# Ethernet.net
KiCad netlist of a schematic drawn in Altium Designer
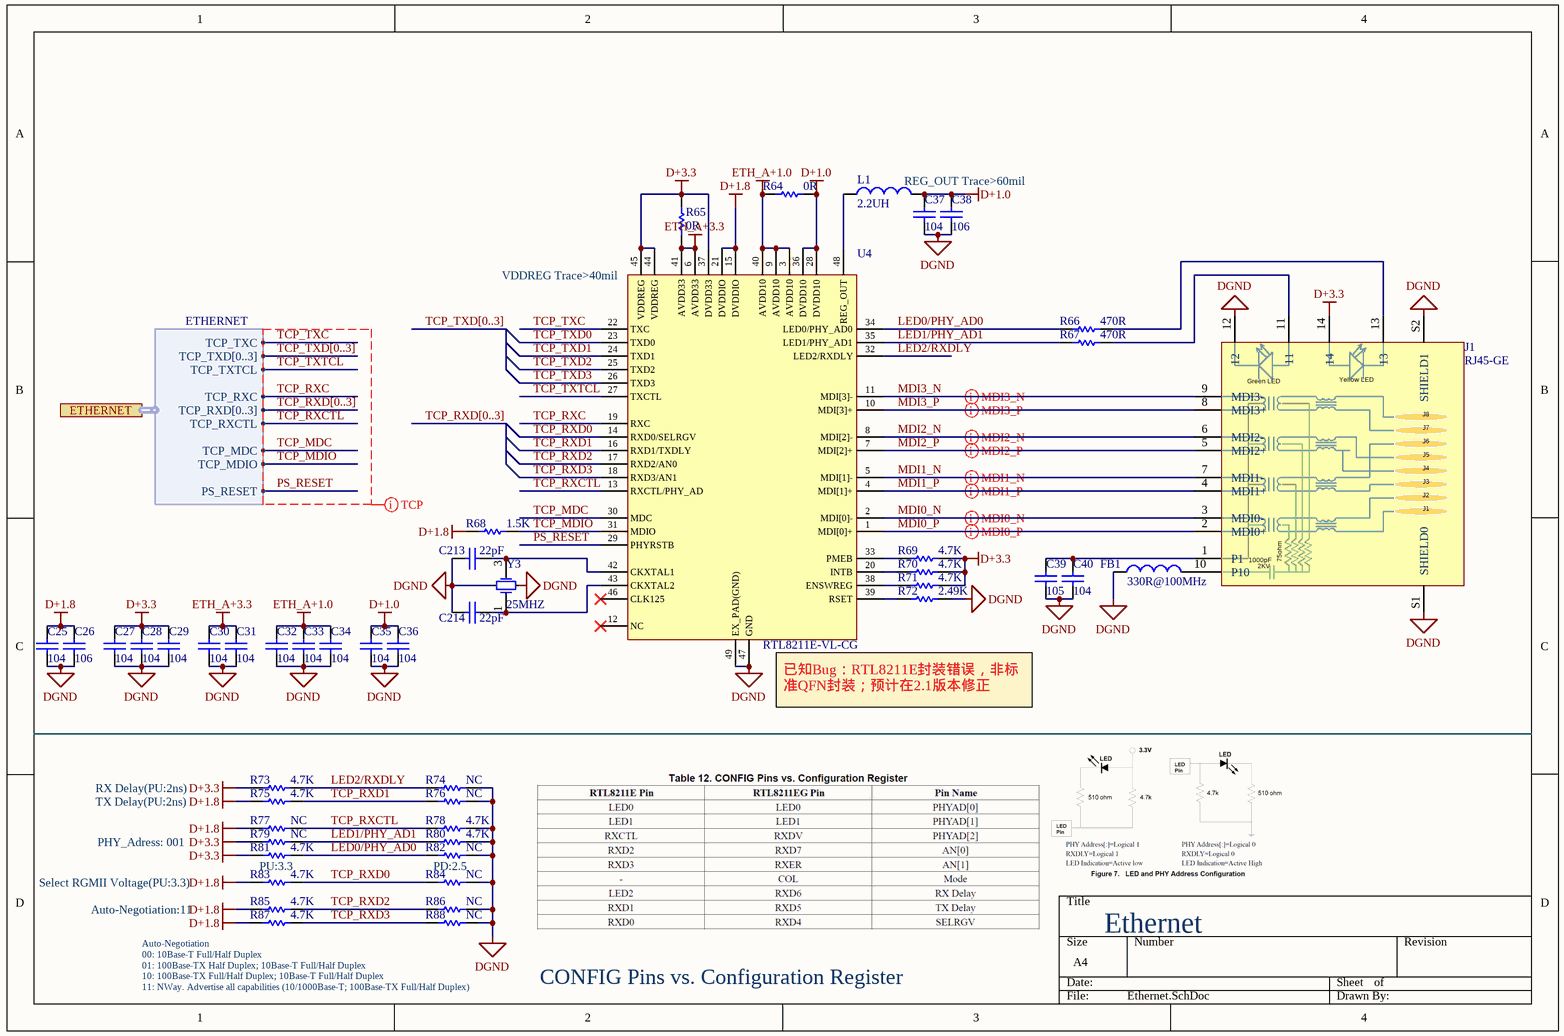
[diagram p0: Ethernet.SchDoc]

(export (version "E")
  (design (tool "Eeschema 10.0.6"))
  (components
    (comp (ref "C25")
      (value "104")
      (footprint "C 0402_LL")
      (description "Capacitor")
      (fields (field (name "PUBLISHER") "Altium Limited"))
      (libsource (lib "Miscellaneous Devices") (part "Cap"))
    )
    (comp (ref "C26")
      (value "106")
      (footprint "C 0603_L")
      (description "Capacitor")
      (fields (field (name "PUBLISHER") "Altium Limited"))
      (libsource (lib "Miscellaneous Devices") (part "Cap"))
    )
    (comp (ref "C27")
      (value "104")
      (footprint "C 0402_LL")
      (description "Capacitor")
      (fields (field (name "PUBLISHER") "Altium Limited"))
      (libsource (lib "Miscellaneous Devices") (part "Cap"))
    )
    (comp (ref "C28")
      (value "104")
      (footprint "C 0402_LL")
      (description "Capacitor")
      (fields (field (name "PUBLISHER") "Altium Limited"))
      (libsource (lib "Miscellaneous Devices") (part "Cap"))
    )
    (comp (ref "C29")
      (value "104")
      (footprint "C 0402_LL")
      (description "Capacitor")
      (fields (field (name "PUBLISHER") "Altium Limited"))
      (libsource (lib "Miscellaneous Devices") (part "Cap"))
    )
    (comp (ref "C30")
      (value "104")
      (footprint "C 0402_LL")
      (description "Capacitor")
      (fields (field (name "PUBLISHER") "Altium Limited"))
      (libsource (lib "Miscellaneous Devices") (part "Cap"))
    )
    (comp (ref "C31")
      (value "104")
      (footprint "C 0402_LL")
      (description "Capacitor")
      (fields (field (name "PUBLISHER") "Altium Limited"))
      (libsource (lib "Miscellaneous Devices") (part "Cap"))
    )
    (comp (ref "C32")
      (value "104")
      (footprint "C 0402_LL")
      (description "Capacitor")
      (fields (field (name "PUBLISHER") "Altium Limited"))
      (libsource (lib "Miscellaneous Devices") (part "Cap"))
    )
    (comp (ref "C33")
      (value "104")
      (footprint "C 0402_LL")
      (description "Capacitor")
      (fields (field (name "PUBLISHER") "Altium Limited"))
      (libsource (lib "Miscellaneous Devices") (part "Cap"))
    )
    (comp (ref "C34")
      (value "104")
      (footprint "C 0402_LL")
      (description "Capacitor")
      (fields (field (name "PUBLISHER") "Altium Limited"))
      (libsource (lib "Miscellaneous Devices") (part "Cap"))
    )
    (comp (ref "C35")
      (value "104")
      (footprint "C 0402_LL")
      (description "Capacitor")
      (fields (field (name "PUBLISHER") "Altium Limited"))
      (libsource (lib "Miscellaneous Devices") (part "Cap"))
    )
    (comp (ref "C36")
      (value "104")
      (footprint "C 0402_LL")
      (description "Capacitor")
      (fields (field (name "PUBLISHER") "Altium Limited"))
      (libsource (lib "Miscellaneous Devices") (part "Cap"))
    )
    (comp (ref "C37")
      (value "104")
      (footprint "C 0402_LL")
      (description "Capacitor")
      (fields (field (name "PUBLISHER") "Altium Limited"))
      (libsource (lib "Miscellaneous Devices") (part "Cap"))
    )
    (comp (ref "C38")
      (value "106")
      (footprint "C 0603_L")
      (description "Capacitor")
      (fields (field (name "PUBLISHER") "Altium Limited"))
      (libsource (lib "Miscellaneous Devices") (part "Cap"))
    )
    (comp (ref "C39")
      (value "105")
      (footprint "C 0603_L")
      (description "Capacitor")
      (fields (field (name "PUBLISHER") "Altium Limited"))
      (libsource (lib "Miscellaneous Devices") (part "Cap"))
    )
    (comp (ref "C40")
      (value "104")
      (footprint "C 0402_LL")
      (description "Capacitor")
      (fields (field (name "PUBLISHER") "Altium Limited"))
      (libsource (lib "Miscellaneous Devices") (part "Cap"))
    )
    (comp (ref "C213")
      (value "22pF")
      (footprint "C 0603_L")
      (description "Capacitor")
      (fields (field (name "PUBLISHER") "Altium Limited"))
      (libsource (lib "Miscellaneous Devices") (part "Cap"))
    )
    (comp (ref "C214")
      (value "22pF")
      (footprint "C 0603_L")
      (description "Capacitor")
      (fields (field (name "PUBLISHER") "Altium Limited"))
      (libsource (lib "Miscellaneous Devices") (part "Cap"))
    )
    (comp (ref "FB1")
      (value "330R@100MHz")
      (footprint "L 0805")
      (description "Inductor")
      (fields (field (name "Comment") "Ferrite Bead") (field (name "PUBLISHER") "Altium Limited"))
      (libsource (lib "Miscellaneous Devices") (part "Inductor"))
    )
    (comp (ref "J1")
      (value "RJ45-GE")
      (footprint "RJ45_10")
      (description "千兆以太网接口（带变压器）")
      (libsource (lib "ZYNQ7010_add") (part "RJ45-GE_re"))
    )
    (comp (ref "L1")
      (value "2.2UH")
      (footprint "NR3010")
      (description "Inductor")
      (fields (field (name "PUBLISHER") "Altium Limited"))
      (libsource (lib "Miscellaneous Devices") (part "Inductor"))
    )
    (comp (ref "R64")
      (value "0R")
      (footprint "R 0603_L")
      (description "Resistor")
      (fields (field (name "PUBLISHER") "Altium Limited"))
      (libsource (lib "Miscellaneous Devices") (part "Res1"))
    )
    (comp (ref "R65")
      (value "0R")
      (footprint "R 0603_L")
      (description "Resistor")
      (fields (field (name "PUBLISHER") "Altium Limited"))
      (libsource (lib "Miscellaneous Devices") (part "Res1"))
    )
    (comp (ref "R66")
      (value "470R")
      (footprint "R 0603_L")
      (description "Resistor")
      (fields (field (name "PUBLISHER") "Altium Limited"))
      (libsource (lib "Miscellaneous Devices") (part "Res1"))
    )
    (comp (ref "R67")
      (value "470R")
      (footprint "R 0603_L")
      (description "Resistor")
      (fields (field (name "PUBLISHER") "Altium Limited"))
      (libsource (lib "Miscellaneous Devices") (part "Res1"))
    )
    (comp (ref "R68")
      (value "1.5K")
      (footprint "R 0603_L")
      (description "Resistor")
      (fields (field (name "PUBLISHER") "Altium Limited"))
      (libsource (lib "Miscellaneous Devices") (part "Res1"))
    )
    (comp (ref "R69")
      (value "4.7K")
      (footprint "R 0402_L")
      (description "Resistor")
      (fields (field (name "PUBLISHER") "Altium Limited"))
      (libsource (lib "Miscellaneous Devices") (part "Res1"))
    )
    (comp (ref "R70")
      (value "4.7K")
      (footprint "R 0402_L")
      (description "Resistor")
      (fields (field (name "PUBLISHER") "Altium Limited"))
      (libsource (lib "Miscellaneous Devices") (part "Res1"))
    )
    (comp (ref "R71")
      (value "4.7K")
      (footprint "R 0402_L")
      (description "Resistor")
      (fields (field (name "PUBLISHER") "Altium Limited"))
      (libsource (lib "Miscellaneous Devices") (part "Res1"))
    )
    (comp (ref "R72")
      (value "2.49K")
      (footprint "R 0603_L")
      (description "Resistor")
      (fields (field (name "PUBLISHER") "Altium Limited"))
      (libsource (lib "Miscellaneous Devices") (part "Res1"))
    )
    (comp (ref "R73")
      (value "4.7K")
      (footprint "R 0402_L")
      (description "Resistor")
      (fields (field (name "PUBLISHER") "Altium Limited"))
      (libsource (lib "Miscellaneous Devices") (part "Res1"))
    )
    (comp (ref "R74")
      (value "NC")
      (footprint "R 0402_L")
      (description "Resistor")
      (fields (field (name "PUBLISHER") "Altium Limited"))
      (libsource (lib "Miscellaneous Devices") (part "Res1"))
    )
    (comp (ref "R75")
      (value "4.7K")
      (footprint "R 0402_L")
      (description "Resistor")
      (fields (field (name "PUBLISHER") "Altium Limited"))
      (libsource (lib "Miscellaneous Devices") (part "Res1"))
    )
    (comp (ref "R76")
      (value "NC")
      (footprint "R 0402_L")
      (description "Resistor")
      (fields (field (name "PUBLISHER") "Altium Limited"))
      (libsource (lib "Miscellaneous Devices") (part "Res1"))
    )
    (comp (ref "R77")
      (value "NC")
      (footprint "R 0402_L")
      (description "Resistor")
      (fields (field (name "PUBLISHER") "Altium Limited"))
      (libsource (lib "Miscellaneous Devices") (part "Res1"))
    )
    (comp (ref "R78")
      (value "4.7K")
      (footprint "R 0402_L")
      (description "Resistor")
      (fields (field (name "PUBLISHER") "Altium Limited"))
      (libsource (lib "Miscellaneous Devices") (part "Res1"))
    )
    (comp (ref "R79")
      (value "NC")
      (footprint "R 0402_L")
      (description "Resistor")
      (fields (field (name "PUBLISHER") "Altium Limited"))
      (libsource (lib "Miscellaneous Devices") (part "Res1"))
    )
    (comp (ref "R80")
      (value "4.7K")
      (footprint "R 0402_L")
      (description "Resistor")
      (fields (field (name "PUBLISHER") "Altium Limited"))
      (libsource (lib "Miscellaneous Devices") (part "Res1"))
    )
    (comp (ref "R81")
      (value "4.7K")
      (footprint "R 0402_L")
      (description "Resistor")
      (fields (field (name "PUBLISHER") "Altium Limited"))
      (libsource (lib "Miscellaneous Devices") (part "Res1"))
    )
    (comp (ref "R82")
      (value "NC")
      (footprint "R 0402_L")
      (description "Resistor")
      (fields (field (name "PUBLISHER") "Altium Limited"))
      (libsource (lib "Miscellaneous Devices") (part "Res1"))
    )
    (comp (ref "R83")
      (value "4.7K")
      (footprint "R 0402_L")
      (description "Resistor")
      (fields (field (name "PUBLISHER") "Altium Limited"))
      (libsource (lib "Miscellaneous Devices") (part "Res1"))
    )
    (comp (ref "R84")
      (value "NC")
      (footprint "R 0402_L")
      (description "Resistor")
      (fields (field (name "PUBLISHER") "Altium Limited"))
      (libsource (lib "Miscellaneous Devices") (part "Res1"))
    )
    (comp (ref "R85")
      (value "4.7K")
      (footprint "R 0402_L")
      (description "Resistor")
      (fields (field (name "PUBLISHER") "Altium Limited"))
      (libsource (lib "Miscellaneous Devices") (part "Res1"))
    )
    (comp (ref "R86")
      (value "NC")
      (footprint "R 0402_L")
      (description "Resistor")
      (fields (field (name "PUBLISHER") "Altium Limited"))
      (libsource (lib "Miscellaneous Devices") (part "Res1"))
    )
    (comp (ref "R87")
      (value "4.7K")
      (footprint "R 0402_L")
      (description "Resistor")
      (fields (field (name "PUBLISHER") "Altium Limited"))
      (libsource (lib "Miscellaneous Devices") (part "Res1"))
    )
    (comp (ref "R88")
      (value "NC")
      (footprint "R 0402_L")
      (description "Resistor")
      (fields (field (name "PUBLISHER") "Altium Limited"))
      (libsource (lib "Miscellaneous Devices") (part "Res1"))
    )
    (comp (ref "U4")
      (value "RTL8211E-VL-CG")
      (footprint "QFN48_RTL8211")
      (description "Ethernet PHY \r\nQFN48(E-VB; E-VL; EG-VB)")
      (libsource (lib "ZYNQ7010_add") (part "RTL8211E"))
    )
    (comp (ref "Y3")
      (value "25MHZ")
      (footprint "OSC 5032-4P")
      (description "无源晶振")
      (fields (field (name "MANUFACTURER") "NC"))
      (libsource (lib "ZYNQ7010_add") (part "XTAL-4-N"))
    )
  )
  (nets
    (net (code "3") (name "/LED0{slash}PHY_AD0") (class "Default")
      (node (ref "R66") (pin "1") (pinfunction "1_1") (pintype "passive"))
      (node (ref "R81") (pin "1") (pinfunction "1_1") (pintype "passive"))
      (node (ref "R82") (pin "2") (pinfunction "2_2") (pintype "passive"))
      (node (ref "U4") (pin "34") (pinfunction "LED0/PHY_AD0_34") (pintype "passive"))
    )
    (net (code "4") (name "/LED1{slash}PHY_AD1") (class "Default")
      (node (ref "R67") (pin "1") (pinfunction "1_1") (pintype "passive"))
      (node (ref "R79") (pin "1") (pinfunction "1_1") (pintype "passive"))
      (node (ref "R80") (pin "2") (pinfunction "2_2") (pintype "passive"))
      (node (ref "U4") (pin "35") (pinfunction "LED1/PHY_AD1_35") (pintype "passive"))
    )
    (net (code "5") (name "/LED2{slash}RXDLY") (class "Default")
      (node (ref "R73") (pin "1") (pinfunction "1_1") (pintype "passive"))
      (node (ref "R74") (pin "2") (pinfunction "2_2") (pintype "passive"))
      (node (ref "U4") (pin "32") (pinfunction "LED2/RXDLY_32") (pintype "passive"))
    )
    (net (code "6") (name "/MDI0_N") (class "Default")
      (node (ref "J1") (pin "3") (pinfunction "MDI0-_3") (pintype "passive"))
      (node (ref "U4") (pin "2") (pinfunction "MDI[0]-_2") (pintype "passive"))
    )
    (net (code "7") (name "/MDI0_P") (class "Default")
      (node (ref "J1") (pin "2") (pinfunction "MDI0+_2") (pintype "passive"))
      (node (ref "U4") (pin "1") (pinfunction "MDI[0]+_1") (pintype "passive"))
    )
    (net (code "8") (name "/MDI1_N") (class "Default")
      (node (ref "J1") (pin "7") (pinfunction "MDI1-_7") (pintype "passive"))
      (node (ref "U4") (pin "5") (pinfunction "MDI[1]-_5") (pintype "passive"))
    )
    (net (code "9") (name "/MDI1_P") (class "Default")
      (node (ref "J1") (pin "4") (pinfunction "MDI1+_4") (pintype "passive"))
      (node (ref "U4") (pin "4") (pinfunction "MDI[1]+_4") (pintype "passive"))
    )
    (net (code "10") (name "/MDI2_N") (class "Default")
      (node (ref "J1") (pin "6") (pinfunction "MDI2-_6") (pintype "passive"))
      (node (ref "U4") (pin "8") (pinfunction "MDI[2]-_8") (pintype "passive"))
    )
    (net (code "11") (name "/MDI2_P") (class "Default")
      (node (ref "J1") (pin "5") (pinfunction "MDI2+_5") (pintype "passive"))
      (node (ref "U4") (pin "7") (pinfunction "MDI[2]+_7") (pintype "passive"))
    )
    (net (code "12") (name "/MDI3_N") (class "Default")
      (node (ref "J1") (pin "9") (pinfunction "MDI3-_9") (pintype "passive"))
      (node (ref "U4") (pin "11") (pinfunction "MDI[3]-_11") (pintype "passive"))
    )
    (net (code "13") (name "/MDI3_P") (class "Default")
      (node (ref "J1") (pin "8") (pinfunction "MDI3+_8") (pintype "passive"))
      (node (ref "U4") (pin "10") (pinfunction "MDI[3]+_10") (pintype "passive"))
    )
    (net (code "14") (name "/PS_RESET") (class "Default")
      (node (ref "U4") (pin "29") (pinfunction "PHYRSTB_29") (pintype "passive"))
    )
    (net (code "15") (name "/TCP_MDC") (class "Default")
      (node (ref "U4") (pin "30") (pinfunction "MDC_30") (pintype "passive"))
    )
    (net (code "16") (name "/TCP_MDIO") (class "Default")
      (node (ref "R68") (pin "1") (pinfunction "1_1") (pintype "passive"))
      (node (ref "U4") (pin "31") (pinfunction "MDIO_31") (pintype "passive"))
    )
    (net (code "17") (name "/TCP_RXC") (class "Default")
      (node (ref "U4") (pin "19") (pinfunction "RXC_19") (pintype "passive"))
    )
    (net (code "18") (name "/TCP_RXCTL") (class "Default")
      (node (ref "R77") (pin "1") (pinfunction "1_1") (pintype "passive"))
      (node (ref "R78") (pin "2") (pinfunction "2_2") (pintype "passive"))
      (node (ref "U4") (pin "13") (pinfunction "RXCTL/PHY_AD_13") (pintype "passive"))
    )
    (net (code "19") (name "/TCP_RXD0") (class "Default")
      (node (ref "R83") (pin "1") (pinfunction "1_1") (pintype "passive"))
      (node (ref "R84") (pin "2") (pinfunction "2_2") (pintype "passive"))
      (node (ref "U4") (pin "14") (pinfunction "RXD0/SELRGV_14") (pintype "passive"))
    )
    (net (code "20") (name "/TCP_RXD1") (class "Default")
      (node (ref "R75") (pin "1") (pinfunction "1_1") (pintype "passive"))
      (node (ref "R76") (pin "2") (pinfunction "2_2") (pintype "passive"))
      (node (ref "U4") (pin "16") (pinfunction "RXD1/TXDLY_16") (pintype "passive"))
    )
    (net (code "21") (name "/TCP_RXD2") (class "Default")
      (node (ref "R85") (pin "1") (pinfunction "1_1") (pintype "passive"))
      (node (ref "R86") (pin "2") (pinfunction "2_2") (pintype "passive"))
      (node (ref "U4") (pin "17") (pinfunction "RXD2/AN0_17") (pintype "passive"))
    )
    (net (code "22") (name "/TCP_RXD3") (class "Default")
      (node (ref "R87") (pin "1") (pinfunction "1_1") (pintype "passive"))
      (node (ref "R88") (pin "2") (pinfunction "2_2") (pintype "passive"))
      (node (ref "U4") (pin "18") (pinfunction "RXD3/AN1_18") (pintype "passive"))
    )
    (net (code "24") (name "/TCP_TXC") (class "Default")
      (node (ref "U4") (pin "22") (pinfunction "TXC_22") (pintype "passive"))
    )
    (net (code "25") (name "/TCP_TXD0") (class "Default")
      (node (ref "U4") (pin "23") (pinfunction "TXD0_23") (pintype "passive"))
    )
    (net (code "26") (name "/TCP_TXD1") (class "Default")
      (node (ref "U4") (pin "24") (pinfunction "TXD1_24") (pintype "passive"))
    )
    (net (code "27") (name "/TCP_TXD2") (class "Default")
      (node (ref "U4") (pin "25") (pinfunction "TXD2_25") (pintype "passive"))
    )
    (net (code "28") (name "/TCP_TXD3") (class "Default")
      (node (ref "U4") (pin "26") (pinfunction "TXD3_26") (pintype "passive"))
    )
    (net (code "30") (name "/TCP_TXTCL") (class "Default")
      (node (ref "U4") (pin "27") (pinfunction "TXCTL_27") (pintype "passive"))
    )
    (net (code "32") (name "D+1.0") (class "Default")
      (node (ref "C35") (pin "1") (pinfunction "1_1") (pintype "passive"))
      (node (ref "C36") (pin "1") (pinfunction "1_1") (pintype "passive"))
      (node (ref "C37") (pin "1") (pinfunction "1_1") (pintype "passive"))
      (node (ref "C38") (pin "1") (pinfunction "1_1") (pintype "passive"))
      (node (ref "L1") (pin "2") (pinfunction "2_2") (pintype "passive"))
      (node (ref "R64") (pin "2") (pinfunction "2_2") (pintype "passive"))
      (node (ref "U4") (pin "28") (pinfunction "DVDD10_28") (pintype "passive"))
      (node (ref "U4") (pin "36") (pinfunction "DVDD10_36") (pintype "passive"))
    )
    (net (code "33") (name "D+1.8") (class "Default")
      (node (ref "C25") (pin "1") (pinfunction "1_1") (pintype "passive"))
      (node (ref "C26") (pin "1") (pinfunction "1_1") (pintype "passive"))
      (node (ref "R68") (pin "2") (pinfunction "2_2") (pintype "passive"))
      (node (ref "R75") (pin "2") (pinfunction "2_2") (pintype "passive"))
      (node (ref "R77") (pin "2") (pinfunction "2_2") (pintype "passive"))
      (node (ref "R83") (pin "2") (pinfunction "2_2") (pintype "passive"))
      (node (ref "R85") (pin "2") (pinfunction "2_2") (pintype "passive"))
      (node (ref "R87") (pin "2") (pinfunction "2_2") (pintype "passive"))
      (node (ref "U4") (pin "15") (pinfunction "DVDDIO_15") (pintype "passive"))
      (node (ref "U4") (pin "21") (pinfunction "DVDDIO_21") (pintype "passive"))
    )
    (net (code "34") (name "D+3.3") (class "Default")
      (node (ref "C27") (pin "1") (pinfunction "1_1") (pintype "passive"))
      (node (ref "C28") (pin "1") (pinfunction "1_1") (pintype "passive"))
      (node (ref "C29") (pin "1") (pinfunction "1_1") (pintype "passive"))
      (node (ref "J1") (pin "14") (pinfunction "14_14") (pintype "passive"))
      (node (ref "R65") (pin "2") (pinfunction "2_2") (pintype "passive"))
      (node (ref "R69") (pin "1") (pinfunction "1_1") (pintype "passive"))
      (node (ref "R70") (pin "1") (pinfunction "1_1") (pintype "passive"))
      (node (ref "R71") (pin "1") (pinfunction "1_1") (pintype "passive"))
      (node (ref "R73") (pin "2") (pinfunction "2_2") (pintype "passive"))
      (node (ref "R79") (pin "2") (pinfunction "2_2") (pintype "passive"))
      (node (ref "R81") (pin "2") (pinfunction "2_2") (pintype "passive"))
      (node (ref "U4") (pin "37") (pinfunction "DVDD33_37") (pintype "passive"))
      (node (ref "U4") (pin "44") (pinfunction "VDDREG_44") (pintype "passive"))
      (node (ref "U4") (pin "45") (pinfunction "VDDREG_45") (pintype "passive"))
    )
    (net (code "35") (name "DGND") (class "Default")
      (node (ref "C213") (pin "1") (pinfunction "1_1") (pintype "passive"))
      (node (ref "C214") (pin "1") (pinfunction "1_1") (pintype "passive"))
      (node (ref "C25") (pin "2") (pinfunction "2_2") (pintype "passive"))
      (node (ref "C26") (pin "2") (pinfunction "2_2") (pintype "passive"))
      (node (ref "C27") (pin "2") (pinfunction "2_2") (pintype "passive"))
      (node (ref "C28") (pin "2") (pinfunction "2_2") (pintype "passive"))
      (node (ref "C29") (pin "2") (pinfunction "2_2") (pintype "passive"))
      (node (ref "C30") (pin "2") (pinfunction "2_2") (pintype "passive"))
      (node (ref "C31") (pin "2") (pinfunction "2_2") (pintype "passive"))
      (node (ref "C32") (pin "2") (pinfunction "2_2") (pintype "passive"))
      (node (ref "C33") (pin "2") (pinfunction "2_2") (pintype "passive"))
      (node (ref "C34") (pin "2") (pinfunction "2_2") (pintype "passive"))
      (node (ref "C35") (pin "2") (pinfunction "2_2") (pintype "passive"))
      (node (ref "C36") (pin "2") (pinfunction "2_2") (pintype "passive"))
      (node (ref "C37") (pin "2") (pinfunction "2_2") (pintype "passive"))
      (node (ref "C38") (pin "2") (pinfunction "2_2") (pintype "passive"))
      (node (ref "C39") (pin "2") (pinfunction "2_2") (pintype "passive"))
      (node (ref "C40") (pin "2") (pinfunction "2_2") (pintype "passive"))
      (node (ref "FB1") (pin "1") (pinfunction "1_1") (pintype "passive"))
      (node (ref "J1") (pin "12") (pinfunction "12_12") (pintype "passive"))
      (node (ref "J1") (pin "S1") (pinfunction "SHIELD0_S1") (pintype "passive"))
      (node (ref "J1") (pin "S2") (pinfunction "SHIELD1_S2") (pintype "passive"))
      (node (ref "R72") (pin "1") (pinfunction "1_1") (pintype "passive"))
      (node (ref "R74") (pin "1") (pinfunction "1_1") (pintype "passive"))
      (node (ref "R76") (pin "1") (pinfunction "1_1") (pintype "passive"))
      (node (ref "R78") (pin "1") (pinfunction "1_1") (pintype "passive"))
      (node (ref "R80") (pin "1") (pinfunction "1_1") (pintype "passive"))
      (node (ref "R82") (pin "1") (pinfunction "1_1") (pintype "passive"))
      (node (ref "R84") (pin "1") (pinfunction "1_1") (pintype "passive"))
      (node (ref "R86") (pin "1") (pinfunction "1_1") (pintype "passive"))
      (node (ref "R88") (pin "1") (pinfunction "1_1") (pintype "passive"))
      (node (ref "U4") (pin "47") (pinfunction "GND_47") (pintype "passive"))
      (node (ref "U4") (pin "49") (pinfunction "EX_PAD(GND)_49") (pintype "passive"))
      (node (ref "Y3") (pin "2") (pinfunction "2_2") (pintype "passive"))
      (node (ref "Y3") (pin "4") (pinfunction "4_4") (pintype "passive"))
    )
    (net (code "36") (name "ETH_A+1.0") (class "Default")
      (node (ref "C32") (pin "1") (pinfunction "1_1") (pintype "passive"))
      (node (ref "C33") (pin "1") (pinfunction "1_1") (pintype "passive"))
      (node (ref "C34") (pin "1") (pinfunction "1_1") (pintype "passive"))
      (node (ref "R64") (pin "1") (pinfunction "1_1") (pintype "passive"))
      (node (ref "U4") (pin "3") (pinfunction "AVDD10_3") (pintype "passive"))
      (node (ref "U4") (pin "40") (pinfunction "AVDD10_40") (pintype "passive"))
      (node (ref "U4") (pin "9") (pinfunction "AVDD10_9") (pintype "passive"))
    )
    (net (code "37") (name "ETH_A+3.3") (class "Default")
      (node (ref "C30") (pin "1") (pinfunction "1_1") (pintype "passive"))
      (node (ref "C31") (pin "1") (pinfunction "1_1") (pintype "passive"))
      (node (ref "R65") (pin "1") (pinfunction "1_1") (pintype "passive"))
      (node (ref "U4") (pin "41") (pinfunction "AVDD33_41") (pintype "passive"))
      (node (ref "U4") (pin "6") (pinfunction "AVDD33_6") (pintype "passive"))
    )
    (net (code "38") (name "Net-(J1-P1)") (class "Default")
      (node (ref "C39") (pin "1") (pinfunction "1_1") (pintype "passive"))
      (node (ref "C40") (pin "1") (pinfunction "1_1") (pintype "passive"))
      (node (ref "J1") (pin "1") (pinfunction "P1_1") (pintype "passive"))
    )
    (net (code "39") (name "Net-(J1-P10)") (class "Default")
      (node (ref "FB1") (pin "2") (pinfunction "2_2") (pintype "passive"))
      (node (ref "J1") (pin "10") (pinfunction "P10_10") (pintype "passive"))
    )
    (net (code "40") (name "Net-(J1-Pad11)") (class "Default")
      (node (ref "J1") (pin "11") (pinfunction "11_11") (pintype "passive"))
      (node (ref "R67") (pin "2") (pinfunction "2_2") (pintype "passive"))
    )
    (net (code "41") (name "Net-(J1-Pad13)") (class "Default")
      (node (ref "J1") (pin "13") (pinfunction "13_13") (pintype "passive"))
      (node (ref "R66") (pin "2") (pinfunction "2_2") (pintype "passive"))
    )
    (net (code "42") (name "Net-(U4-CKXTAL1)") (class "Default")
      (node (ref "C213") (pin "2") (pinfunction "2_2") (pintype "passive"))
      (node (ref "U4") (pin "42") (pinfunction "CKXTAL1_42") (pintype "passive"))
      (node (ref "Y3") (pin "3") (pinfunction "OSC2_3") (pintype "passive"))
    )
    (net (code "43") (name "Net-(U4-CKXTAL2)") (class "Default")
      (node (ref "C214") (pin "2") (pinfunction "2_2") (pintype "passive"))
      (node (ref "U4") (pin "43") (pinfunction "CKXTAL2_43") (pintype "passive"))
      (node (ref "Y3") (pin "1") (pinfunction "OSC1_1") (pintype "passive"))
    )
    (net (code "44") (name "Net-(U4-ENSWREG)") (class "Default")
      (node (ref "R71") (pin "2") (pinfunction "2_2") (pintype "passive"))
      (node (ref "U4") (pin "38") (pinfunction "ENSWREG_38") (pintype "passive"))
    )
    (net (code "45") (name "Net-(U4-INTB)") (class "Default")
      (node (ref "R70") (pin "2") (pinfunction "2_2") (pintype "passive"))
      (node (ref "U4") (pin "20") (pinfunction "INTB_20") (pintype "passive"))
    )
    (net (code "46") (name "Net-(U4-PMEB)") (class "Default")
      (node (ref "R69") (pin "2") (pinfunction "2_2") (pintype "passive"))
      (node (ref "U4") (pin "33") (pinfunction "PMEB_33") (pintype "passive"))
    )
    (net (code "47") (name "Net-(U4-REG_OUT)") (class "Default")
      (node (ref "L1") (pin "1") (pinfunction "1_1") (pintype "passive"))
      (node (ref "U4") (pin "48") (pinfunction "REG_OUT_48") (pintype "passive"))
    )
    (net (code "48") (name "Net-(U4-RSET)") (class "Default")
      (node (ref "R72") (pin "2") (pinfunction "2_2") (pintype "passive"))
      (node (ref "U4") (pin "39") (pinfunction "RSET_39") (pintype "passive"))
    )
    (net (code "49") (name "unconnected-(U4-CLK125-Pad46)") (class "Default")
      (node (ref "U4") (pin "46") (pinfunction "CLK125_46") (pintype "passive+no_connect"))
    )
    (net (code "50") (name "unconnected-(U4-NC-Pad12)") (class "Default")
      (node (ref "U4") (pin "12") (pinfunction "NC_12") (pintype "passive+no_connect"))
    )
  )
)
